# CrashButtonESP8266D1.net
KiCad netlist of a schematic drawn in EAGLE
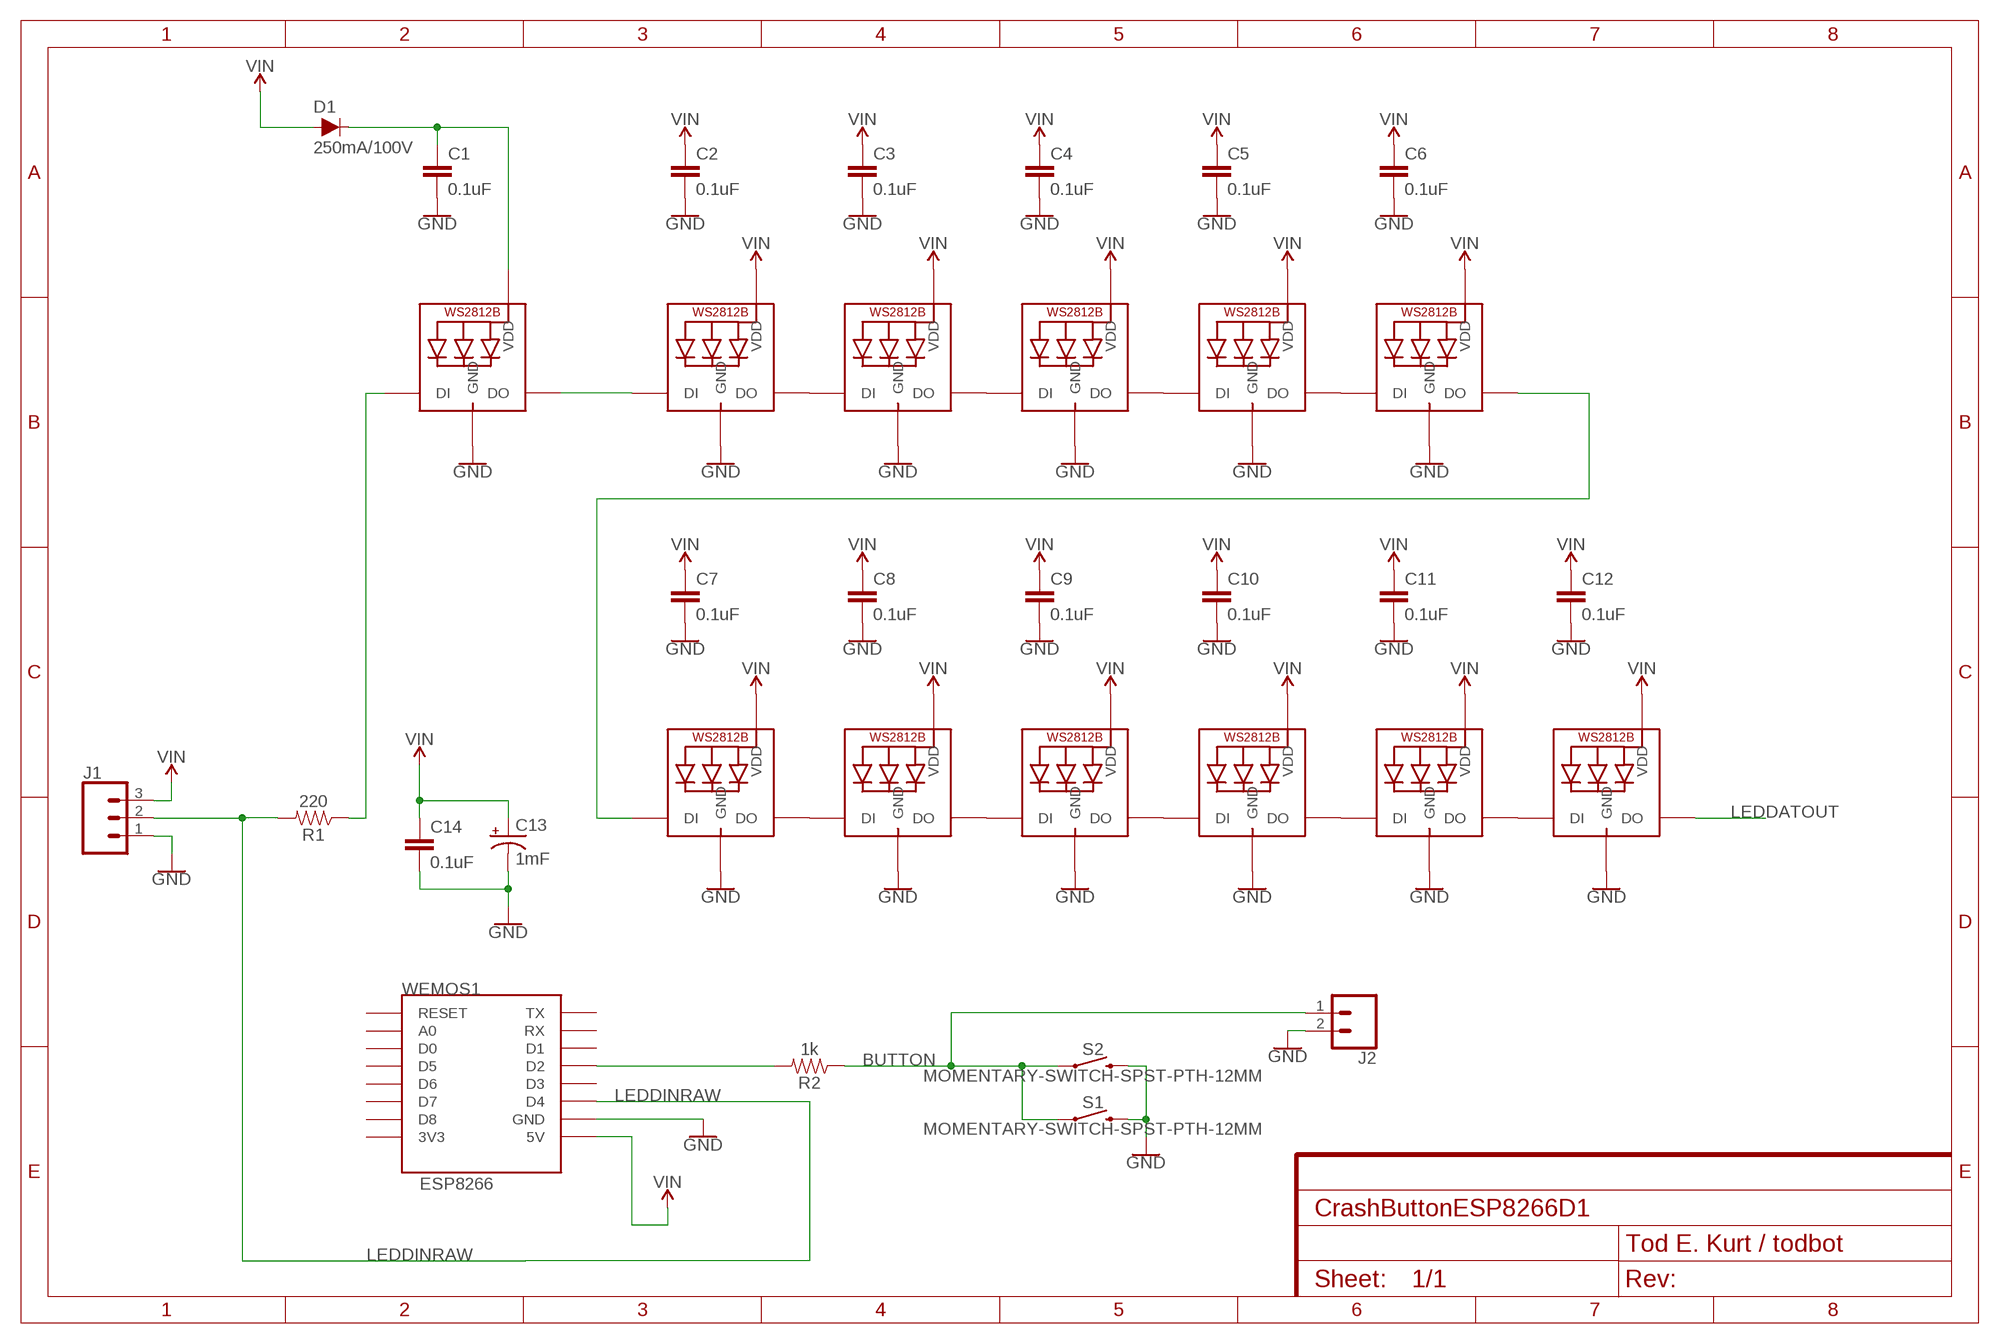
[diagram p0: schematic, sheet 1]

(export (version "E")
  (design (tool "Eeschema 10.0.6"))
  (components
    (comp (ref "C1")
      (value "0.1uF")
      (footprint "eagle-import:0603")
      (libsource (lib "eagle-import") (part "0.1UF-0603-25V-(+80/-20%)"))
    )
    (comp (ref "C2")
      (value "0.1uF")
      (footprint "eagle-import:0603")
      (libsource (lib "eagle-import") (part "0.1UF-0603-25V-(+80/-20%)"))
    )
    (comp (ref "C3")
      (value "0.1uF")
      (footprint "eagle-import:0603")
      (libsource (lib "eagle-import") (part "0.1UF-0603-25V-(+80/-20%)"))
    )
    (comp (ref "C4")
      (value "0.1uF")
      (footprint "eagle-import:0603")
      (libsource (lib "eagle-import") (part "0.1UF-0603-25V-(+80/-20%)"))
    )
    (comp (ref "C5")
      (value "0.1uF")
      (footprint "eagle-import:0603")
      (libsource (lib "eagle-import") (part "0.1UF-0603-25V-(+80/-20%)"))
    )
    (comp (ref "C6")
      (value "0.1uF")
      (footprint "eagle-import:0603")
      (libsource (lib "eagle-import") (part "0.1UF-0603-25V-(+80/-20%)"))
    )
    (comp (ref "C7")
      (value "0.1uF")
      (footprint "eagle-import:0603")
      (libsource (lib "eagle-import") (part "0.1UF-0603-25V-(+80/-20%)"))
    )
    (comp (ref "C8")
      (value "0.1uF")
      (footprint "eagle-import:0603")
      (libsource (lib "eagle-import") (part "0.1UF-0603-25V-(+80/-20%)"))
    )
    (comp (ref "C9")
      (value "0.1uF")
      (footprint "eagle-import:0603")
      (libsource (lib "eagle-import") (part "0.1UF-0603-25V-(+80/-20%)"))
    )
    (comp (ref "C10")
      (value "0.1uF")
      (footprint "eagle-import:0603")
      (libsource (lib "eagle-import") (part "0.1UF-0603-25V-(+80/-20%)"))
    )
    (comp (ref "C11")
      (value "0.1uF")
      (footprint "eagle-import:0603")
      (libsource (lib "eagle-import") (part "0.1UF-0603-25V-(+80/-20%)"))
    )
    (comp (ref "C12")
      (value "0.1uF")
      (footprint "eagle-import:0603")
      (libsource (lib "eagle-import") (part "0.1UF-0603-25V-(+80/-20%)"))
    )
    (comp (ref "C13")
      (value "1mF")
      (footprint "eagle-import:CPOL-RADIAL-5MM-10MM")
      (libsource (lib "eagle-import") (part "1000UF-RADIAL-5MM-25V-20%"))
    )
    (comp (ref "C14")
      (value "0.1uF")
      (footprint "eagle-import:0603")
      (libsource (lib "eagle-import") (part "0.1UF-0603-25V-(+80/-20%)"))
    )
    (comp (ref "D1")
      (value "250mA/100V")
      (footprint "eagle-import:SOD-323")
      (libsource (lib "eagle-import") (part "DIODE-BAS16J"))
    )
    (comp (ref "J1")
      (value "CONN_03")
      (footprint "eagle-import:1X03")
      (libsource (lib "eagle-import") (part "CONN_03"))
    )
    (comp (ref "J2")
      (value "CONN_02")
      (footprint "eagle-import:1X02")
      (libsource (lib "eagle-import") (part "CONN_02"))
    )
    (comp (ref "LED1")
      (value "WS2812B5050")
      (footprint "eagle-import:WS2812B")
      (libsource (lib "eagle-import") (part "WS2812B5050"))
    )
    (comp (ref "LED2")
      (value "WS2812B5050")
      (footprint "eagle-import:WS2812B")
      (libsource (lib "eagle-import") (part "WS2812B5050"))
    )
    (comp (ref "LED3")
      (value "WS2812B5050")
      (footprint "eagle-import:WS2812B")
      (libsource (lib "eagle-import") (part "WS2812B5050"))
    )
    (comp (ref "LED4")
      (value "WS2812B5050")
      (footprint "eagle-import:WS2812B")
      (libsource (lib "eagle-import") (part "WS2812B5050"))
    )
    (comp (ref "LED5")
      (value "WS2812B5050")
      (footprint "eagle-import:WS2812B")
      (libsource (lib "eagle-import") (part "WS2812B5050"))
    )
    (comp (ref "LED6")
      (value "WS2812B5050")
      (footprint "eagle-import:WS2812B")
      (libsource (lib "eagle-import") (part "WS2812B5050"))
    )
    (comp (ref "LED7")
      (value "WS2812B5050")
      (footprint "eagle-import:WS2812B")
      (libsource (lib "eagle-import") (part "WS2812B5050"))
    )
    (comp (ref "LED8")
      (value "WS2812B5050")
      (footprint "eagle-import:WS2812B")
      (libsource (lib "eagle-import") (part "WS2812B5050"))
    )
    (comp (ref "LED9")
      (value "WS2812B5050")
      (footprint "eagle-import:WS2812B")
      (libsource (lib "eagle-import") (part "WS2812B5050"))
    )
    (comp (ref "LED10")
      (value "WS2812B5050")
      (footprint "eagle-import:WS2812B")
      (libsource (lib "eagle-import") (part "WS2812B5050"))
    )
    (comp (ref "LED11")
      (value "WS2812B5050")
      (footprint "eagle-import:WS2812B")
      (libsource (lib "eagle-import") (part "WS2812B5050"))
    )
    (comp (ref "LED12")
      (value "WS2812B5050")
      (footprint "eagle-import:WS2812B")
      (libsource (lib "eagle-import") (part "WS2812B5050"))
    )
    (comp (ref "R1")
      (value "220")
      (footprint "eagle-import:0603")
      (libsource (lib "eagle-import") (part "470OHM-0603-1/10W-1%"))
    )
    (comp (ref "R2")
      (value "1k")
      (footprint "eagle-import:0603")
      (libsource (lib "eagle-import") (part "470OHM-0603-1/10W-1%"))
    )
    (comp (ref "S1")
      (value "MOMENTARY-SWITCH-SPST-PTH-12MM")
      (footprint "eagle-import:TACTILE_SWITCH_PTH_12MM")
      (libsource (lib "eagle-import") (part "MOMENTARY-SWITCH-SPST-PTH-12MM"))
    )
    (comp (ref "S2")
      (value "MOMENTARY-SWITCH-SPST-PTH-12MM")
      (footprint "eagle-import:TACTILE_SWITCH_PTH_12MM")
      (libsource (lib "eagle-import") (part "MOMENTARY-SWITCH-SPST-PTH-12MM"))
    )
    (comp (ref "WEMOS1")
      (value "ESP8266")
      (footprint "eagle-import:WEMOS-D1-MINI")
      (libsource (lib "eagle-import") (part "WEMOS-D1-MINI"))
    )
  )
  (nets
    (net (code "1") (name "/BUTTON") (class "Default")
      (node (ref "J2") (pin "1") (pinfunction "1_1") (pintype "passive"))
      (node (ref "R2") (pin "1") (pinfunction "1_1") (pintype "passive"))
      (node (ref "S1") (pin "1") (pinfunction "1_1") (pintype "passive"))
      (node (ref "S2") (pin "1") (pinfunction "1_1") (pintype "passive"))
    )
    (net (code "2") (name "/LEDDATOUT") (class "Default")
      (node (ref "LED12") (pin "2-DOUT") (pinfunction "DO_2-DOUT") (pintype "output"))
    )
    (net (code "3") (name "/LEDDINRAW") (class "Default")
      (node (ref "J1") (pin "2") (pinfunction "2_2") (pintype "passive"))
      (node (ref "R1") (pin "2") (pinfunction "2_2") (pintype "passive"))
      (node (ref "WEMOS1") (pin "D4") (pinfunction "D4_D4") (pintype "bidirectional"))
    )
    (net (code "4") (name "GND") (class "Default")
      (node (ref "C1") (pin "2") (pinfunction "2_2") (pintype "passive"))
      (node (ref "C10") (pin "2") (pinfunction "2_2") (pintype "passive"))
      (node (ref "C11") (pin "2") (pinfunction "2_2") (pintype "passive"))
      (node (ref "C12") (pin "2") (pinfunction "2_2") (pintype "passive"))
      (node (ref "C13") (pin "-") (pinfunction "-_-") (pintype "passive"))
      (node (ref "C14") (pin "2") (pinfunction "2_2") (pintype "passive"))
      (node (ref "C2") (pin "2") (pinfunction "2_2") (pintype "passive"))
      (node (ref "C3") (pin "2") (pinfunction "2_2") (pintype "passive"))
      (node (ref "C4") (pin "2") (pinfunction "2_2") (pintype "passive"))
      (node (ref "C5") (pin "2") (pinfunction "2_2") (pintype "passive"))
      (node (ref "C6") (pin "2") (pinfunction "2_2") (pintype "passive"))
      (node (ref "C7") (pin "2") (pinfunction "2_2") (pintype "passive"))
      (node (ref "C8") (pin "2") (pinfunction "2_2") (pintype "passive"))
      (node (ref "C9") (pin "2") (pinfunction "2_2") (pintype "passive"))
      (node (ref "J1") (pin "1") (pinfunction "1_1") (pintype "passive"))
      (node (ref "J2") (pin "2") (pinfunction "2_2") (pintype "passive"))
      (node (ref "LED1") (pin "3-GND") (pinfunction "GND_3-GND") (pintype "power_in"))
      (node (ref "LED10") (pin "3-GND") (pinfunction "GND_3-GND") (pintype "power_in"))
      (node (ref "LED11") (pin "3-GND") (pinfunction "GND_3-GND") (pintype "power_in"))
      (node (ref "LED12") (pin "3-GND") (pinfunction "GND_3-GND") (pintype "power_in"))
      (node (ref "LED2") (pin "3-GND") (pinfunction "GND_3-GND") (pintype "power_in"))
      (node (ref "LED3") (pin "3-GND") (pinfunction "GND_3-GND") (pintype "power_in"))
      (node (ref "LED4") (pin "3-GND") (pinfunction "GND_3-GND") (pintype "power_in"))
      (node (ref "LED5") (pin "3-GND") (pinfunction "GND_3-GND") (pintype "power_in"))
      (node (ref "LED6") (pin "3-GND") (pinfunction "GND_3-GND") (pintype "power_in"))
      (node (ref "LED7") (pin "3-GND") (pinfunction "GND_3-GND") (pintype "power_in"))
      (node (ref "LED8") (pin "3-GND") (pinfunction "GND_3-GND") (pintype "power_in"))
      (node (ref "LED9") (pin "3-GND") (pinfunction "GND_3-GND") (pintype "power_in"))
      (node (ref "S1") (pin "3") (pinfunction "2_3") (pintype "passive"))
      (node (ref "S2") (pin "3") (pinfunction "2_3") (pintype "passive"))
      (node (ref "WEMOS1") (pin "GND") (pinfunction "GND_GND") (pintype "bidirectional"))
    )
    (net (code "5") (name "Net-(LED1-DI)") (class "Default")
      (node (ref "LED1") (pin "4-DIN") (pinfunction "DI_4-DIN") (pintype "input"))
      (node (ref "R1") (pin "1") (pinfunction "1_1") (pintype "passive"))
    )
    (net (code "6") (name "Net-(LED1-DO)") (class "Default")
      (node (ref "LED1") (pin "2-DOUT") (pinfunction "DO_2-DOUT") (pintype "output"))
      (node (ref "LED2") (pin "4-DIN") (pinfunction "DI_4-DIN") (pintype "input"))
    )
    (net (code "7") (name "Net-(LED1-VDD)") (class "Default")
      (node (ref "C1") (pin "1") (pinfunction "1_1") (pintype "passive"))
      (node (ref "D1") (pin "C") (pinfunction "C_C") (pintype "passive"))
      (node (ref "LED1") (pin "1-VDD") (pinfunction "VDD_1-VDD") (pintype "power_in"))
    )
    (net (code "8") (name "Net-(LED2-DO)") (class "Default")
      (node (ref "LED2") (pin "2-DOUT") (pinfunction "DO_2-DOUT") (pintype "output"))
      (node (ref "LED3") (pin "4-DIN") (pinfunction "DI_4-DIN") (pintype "input"))
    )
    (net (code "9") (name "Net-(LED3-DO)") (class "Default")
      (node (ref "LED3") (pin "2-DOUT") (pinfunction "DO_2-DOUT") (pintype "output"))
      (node (ref "LED4") (pin "4-DIN") (pinfunction "DI_4-DIN") (pintype "input"))
    )
    (net (code "10") (name "Net-(LED4-DO)") (class "Default")
      (node (ref "LED4") (pin "2-DOUT") (pinfunction "DO_2-DOUT") (pintype "output"))
      (node (ref "LED5") (pin "4-DIN") (pinfunction "DI_4-DIN") (pintype "input"))
    )
    (net (code "11") (name "Net-(LED5-DO)") (class "Default")
      (node (ref "LED5") (pin "2-DOUT") (pinfunction "DO_2-DOUT") (pintype "output"))
      (node (ref "LED6") (pin "4-DIN") (pinfunction "DI_4-DIN") (pintype "input"))
    )
    (net (code "12") (name "Net-(LED6-DO)") (class "Default")
      (node (ref "LED6") (pin "2-DOUT") (pinfunction "DO_2-DOUT") (pintype "output"))
      (node (ref "LED7") (pin "4-DIN") (pinfunction "DI_4-DIN") (pintype "input"))
    )
    (net (code "13") (name "Net-(LED7-DO)") (class "Default")
      (node (ref "LED7") (pin "2-DOUT") (pinfunction "DO_2-DOUT") (pintype "output"))
      (node (ref "LED8") (pin "4-DIN") (pinfunction "DI_4-DIN") (pintype "input"))
    )
    (net (code "14") (name "Net-(LED8-DO)") (class "Default")
      (node (ref "LED8") (pin "2-DOUT") (pinfunction "DO_2-DOUT") (pintype "output"))
      (node (ref "LED9") (pin "4-DIN") (pinfunction "DI_4-DIN") (pintype "input"))
    )
    (net (code "15") (name "Net-(LED10-DI)") (class "Default")
      (node (ref "LED10") (pin "4-DIN") (pinfunction "DI_4-DIN") (pintype "input"))
      (node (ref "LED9") (pin "2-DOUT") (pinfunction "DO_2-DOUT") (pintype "output"))
    )
    (net (code "16") (name "Net-(LED10-DO)") (class "Default")
      (node (ref "LED10") (pin "2-DOUT") (pinfunction "DO_2-DOUT") (pintype "output"))
      (node (ref "LED11") (pin "4-DIN") (pinfunction "DI_4-DIN") (pintype "input"))
    )
    (net (code "17") (name "Net-(LED11-DO)") (class "Default")
      (node (ref "LED11") (pin "2-DOUT") (pinfunction "DO_2-DOUT") (pintype "output"))
      (node (ref "LED12") (pin "4-DIN") (pinfunction "DI_4-DIN") (pintype "input"))
    )
    (net (code "18") (name "Net-(R2-Pad2)") (class "Default")
      (node (ref "R2") (pin "2") (pinfunction "2_2") (pintype "passive"))
      (node (ref "WEMOS1") (pin "D2") (pinfunction "D2_D2") (pintype "bidirectional"))
    )
    (net (code "19") (name "VIN") (class "Default")
      (node (ref "C10") (pin "1") (pinfunction "1_1") (pintype "passive"))
      (node (ref "C11") (pin "1") (pinfunction "1_1") (pintype "passive"))
      (node (ref "C12") (pin "1") (pinfunction "1_1") (pintype "passive"))
      (node (ref "C13") (pin "+") (pinfunction "+_+") (pintype "passive"))
      (node (ref "C14") (pin "1") (pinfunction "1_1") (pintype "passive"))
      (node (ref "C2") (pin "1") (pinfunction "1_1") (pintype "passive"))
      (node (ref "C3") (pin "1") (pinfunction "1_1") (pintype "passive"))
      (node (ref "C4") (pin "1") (pinfunction "1_1") (pintype "passive"))
      (node (ref "C5") (pin "1") (pinfunction "1_1") (pintype "passive"))
      (node (ref "C6") (pin "1") (pinfunction "1_1") (pintype "passive"))
      (node (ref "C7") (pin "1") (pinfunction "1_1") (pintype "passive"))
      (node (ref "C8") (pin "1") (pinfunction "1_1") (pintype "passive"))
      (node (ref "C9") (pin "1") (pinfunction "1_1") (pintype "passive"))
      (node (ref "D1") (pin "A") (pinfunction "A_A") (pintype "passive"))
      (node (ref "J1") (pin "3") (pinfunction "3_3") (pintype "passive"))
      (node (ref "LED10") (pin "1-VDD") (pinfunction "VDD_1-VDD") (pintype "power_in"))
      (node (ref "LED11") (pin "1-VDD") (pinfunction "VDD_1-VDD") (pintype "power_in"))
      (node (ref "LED12") (pin "1-VDD") (pinfunction "VDD_1-VDD") (pintype "power_in"))
      (node (ref "LED2") (pin "1-VDD") (pinfunction "VDD_1-VDD") (pintype "power_in"))
      (node (ref "LED3") (pin "1-VDD") (pinfunction "VDD_1-VDD") (pintype "power_in"))
      (node (ref "LED4") (pin "1-VDD") (pinfunction "VDD_1-VDD") (pintype "power_in"))
      (node (ref "LED5") (pin "1-VDD") (pinfunction "VDD_1-VDD") (pintype "power_in"))
      (node (ref "LED6") (pin "1-VDD") (pinfunction "VDD_1-VDD") (pintype "power_in"))
      (node (ref "LED7") (pin "1-VDD") (pinfunction "VDD_1-VDD") (pintype "power_in"))
      (node (ref "LED8") (pin "1-VDD") (pinfunction "VDD_1-VDD") (pintype "power_in"))
      (node (ref "LED9") (pin "1-VDD") (pinfunction "VDD_1-VDD") (pintype "power_in"))
      (node (ref "WEMOS1") (pin "5V") (pinfunction "5V_5V") (pintype "bidirectional"))
    )
    (net (code "20") (name "unconnected-(WEMOS1-Pad3V3)") (class "Default")
      (node (ref "WEMOS1") (pin "3V3") (pinfunction "3V3_3V3") (pintype "bidirectional"))
    )
    (net (code "21") (name "unconnected-(WEMOS1-PadA0)") (class "Default")
      (node (ref "WEMOS1") (pin "A0") (pinfunction "A0_A0") (pintype "bidirectional"))
    )
    (net (code "22") (name "unconnected-(WEMOS1-PadD0)") (class "Default")
      (node (ref "WEMOS1") (pin "D0") (pinfunction "D0_D0") (pintype "bidirectional"))
    )
    (net (code "23") (name "unconnected-(WEMOS1-PadD1)") (class "Default")
      (node (ref "WEMOS1") (pin "D1") (pinfunction "D1_D1") (pintype "bidirectional"))
    )
    (net (code "24") (name "unconnected-(WEMOS1-PadD3)") (class "Default")
      (node (ref "WEMOS1") (pin "D3") (pinfunction "D3_D3") (pintype "bidirectional"))
    )
    (net (code "25") (name "unconnected-(WEMOS1-PadD5)") (class "Default")
      (node (ref "WEMOS1") (pin "D5") (pinfunction "D5_D5") (pintype "bidirectional"))
    )
    (net (code "26") (name "unconnected-(WEMOS1-PadD6)") (class "Default")
      (node (ref "WEMOS1") (pin "D6") (pinfunction "D6_D6") (pintype "bidirectional"))
    )
    (net (code "27") (name "unconnected-(WEMOS1-PadD7)") (class "Default")
      (node (ref "WEMOS1") (pin "D7") (pinfunction "D7_D7") (pintype "bidirectional"))
    )
    (net (code "28") (name "unconnected-(WEMOS1-PadD8)") (class "Default")
      (node (ref "WEMOS1") (pin "D8") (pinfunction "D8_D8") (pintype "bidirectional"))
    )
    (net (code "29") (name "unconnected-(WEMOS1-PadRESET)") (class "Default")
      (node (ref "WEMOS1") (pin "RESET") (pinfunction "RESET_RESET") (pintype "bidirectional"))
    )
    (net (code "30") (name "unconnected-(WEMOS1-PadRX)") (class "Default")
      (node (ref "WEMOS1") (pin "RX") (pinfunction "RX_RX") (pintype "bidirectional"))
    )
    (net (code "31") (name "unconnected-(WEMOS1-PadTX)") (class "Default")
      (node (ref "WEMOS1") (pin "TX") (pinfunction "TX_TX") (pintype "bidirectional"))
    )
  )
)
